# ScrollingTextDisplay.net
KiCad netlist of a schematic drawn in EAGLE
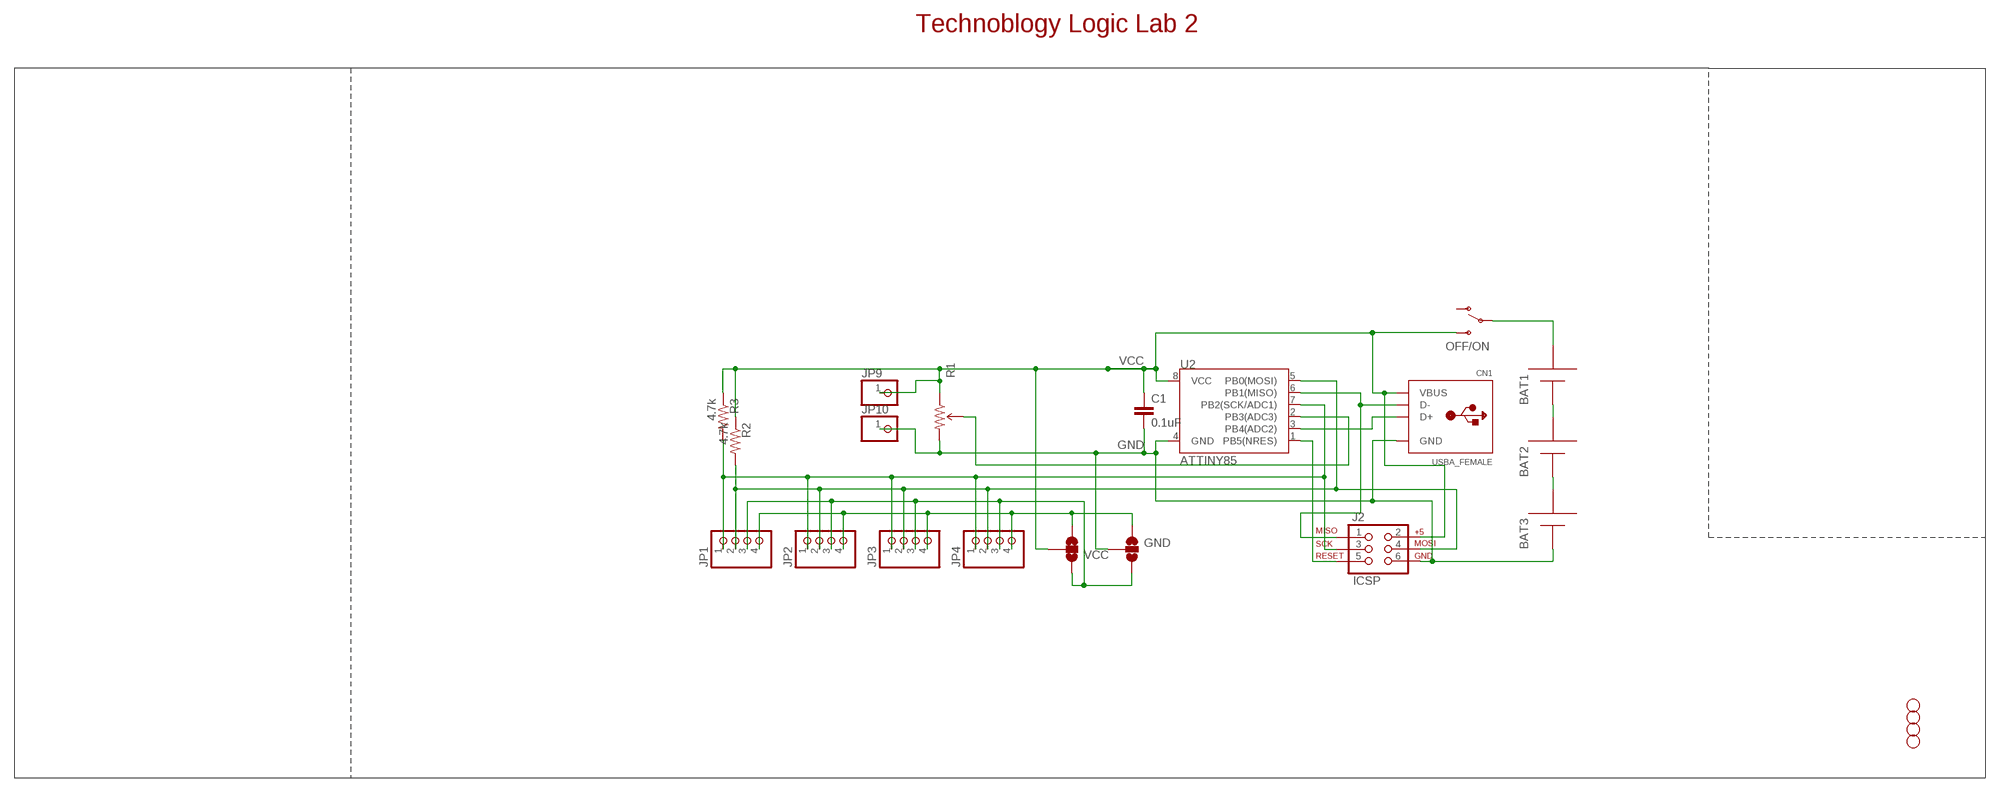
[diagram p0: schematic, sheet 1]

(export (version "E")
  (design (tool "Eeschema 10.0.6"))
  (components
    (comp (ref "BAT1")
      (value "AAA")
      (footprint "eagle-import:12BH412")
      (libsource (lib "eagle-import") (part "AAA"))
    )
    (comp (ref "BAT2")
      (value "AAA")
      (footprint "eagle-import:12BH412")
      (libsource (lib "eagle-import") (part "AAA"))
    )
    (comp (ref "BAT3")
      (value "AAA")
      (footprint "eagle-import:12BH412")
      (libsource (lib "eagle-import") (part "AAA"))
    )
    (comp (ref "C1")
      (value "0.1uF")
      (footprint "eagle-import:CAP-PTH-SMALL-KIT")
      (libsource (lib "eagle-import") (part "0.1UF-50V-20%(PTH)KIT-EZ"))
    )
    (comp (ref "CN1")
      (value "USBA_FEMALE")
      (footprint "eagle-import:USB_HOST-PTH")
      (libsource (lib "eagle-import") (part "USB_TYPEAPTHFML"))
    )
    (comp (ref "GND")
      (value "JUMPER-PAD-3-NOFULL_BOX_SILK")
      (footprint "eagle-import:PAD-JUMPER-3-NO_YES_SILK_FULL_BOX")
      (libsource (lib "eagle-import") (part "JUMPER-PAD-3-NOFULL_BOX_SILK"))
    )
    (comp (ref "J2")
      (value "ICSP")
      (footprint "eagle-import:2X3")
      (libsource (lib "eagle-import") (part "AVR_SPI_PRG_6PTH"))
    )
    (comp (ref "JP1")
      (value "HEADER-1X4ROUND")
      (footprint "eagle-import:1X04_ROUND")
      (libsource (lib "eagle-import") (part "HEADER-1X4ROUND"))
    )
    (comp (ref "JP2")
      (value "HEADER-1X4ROUND")
      (footprint "eagle-import:1X04_ROUND")
      (libsource (lib "eagle-import") (part "HEADER-1X4ROUND"))
    )
    (comp (ref "JP3")
      (value "HEADER-1X4ROUND")
      (footprint "eagle-import:1X04_ROUND")
      (libsource (lib "eagle-import") (part "HEADER-1X4ROUND"))
    )
    (comp (ref "JP4")
      (value "HEADER-1X4ROUND")
      (footprint "eagle-import:1X04_ROUND")
      (libsource (lib "eagle-import") (part "HEADER-1X4ROUND"))
    )
    (comp (ref "JP5")
      (value "STAND-OFF")
      (footprint "eagle-import:STAND-OFF")
      (libsource (lib "eagle-import") (part "STAND-OFF"))
    )
    (comp (ref "JP6")
      (value "STAND-OFF")
      (footprint "eagle-import:STAND-OFF")
      (libsource (lib "eagle-import") (part "STAND-OFF"))
    )
    (comp (ref "JP7")
      (value "STAND-OFF")
      (footprint "eagle-import:STAND-OFF")
      (libsource (lib "eagle-import") (part "STAND-OFF"))
    )
    (comp (ref "JP8")
      (value "STAND-OFF")
      (footprint "eagle-import:STAND-OFF")
      (libsource (lib "eagle-import") (part "STAND-OFF"))
    )
    (comp (ref "JP9")
      (value "HEADER-1X1ROUND")
      (footprint "eagle-import:1X01_ROUND")
      (libsource (lib "eagle-import") (part "HEADER-1X1ROUND"))
    )
    (comp (ref "JP10")
      (value "HEADER-1X1ROUND")
      (footprint "eagle-import:1X01_ROUND")
      (libsource (lib "eagle-import") (part "HEADER-1X1ROUND"))
    )
    (comp (ref "OFF/ON")
      (value "SWITCH-SPDTKIT")
      (footprint "eagle-import:SWITCH-SPDT_KIT")
      (libsource (lib "eagle-import") (part "SWITCH-SPDTKIT"))
    )
    (comp (ref "R1")
      (value "TRIMPOTPTH")
      (footprint "eagle-import:TRIM_POT_PTH")
      (libsource (lib "eagle-import") (part "TRIMPOTPTH"))
    )
    (comp (ref "R2")
      (value "4.7k")
      (footprint "eagle-import:AXIAL-0.3")
      (libsource (lib "eagle-import") (part "RESISTORAXIAL-0.3"))
    )
    (comp (ref "R3")
      (value "4.7k")
      (footprint "eagle-import:AXIAL-0.3")
      (libsource (lib "eagle-import") (part "RESISTORAXIAL-0.3"))
    )
    (comp (ref "U2")
      (value "ATTINY85")
      (footprint "eagle-import:DIP08")
      (libsource (lib "eagle-import") (part "ATTINY45TINY85-20-DIP"))
    )
    (comp (ref "VCC")
      (value "JUMPER-PAD-3-NOFULL_BOX_SILK")
      (footprint "eagle-import:PAD-JUMPER-3-NO_YES_SILK_FULL_BOX")
      (libsource (lib "eagle-import") (part "JUMPER-PAD-3-NOFULL_BOX_SILK"))
    )
  )
  (nets
    (net (code "1") (name "/GND") (class "Default")
      (node (ref "BAT3") (pin "-") (pinfunction "-_-") (pintype "bidirectional"))
      (node (ref "C1") (pin "2") (pinfunction "2_2") (pintype "passive"))
      (node (ref "CN1") (pin "GND") (pinfunction "GND_GND") (pintype "power_in"))
      (node (ref "GND") (pin "2") (pinfunction "2_2") (pintype "passive"))
      (node (ref "J2") (pin "6") (pinfunction "6_6") (pintype "passive"))
      (node (ref "JP10") (pin "1") (pinfunction "1_1") (pintype "passive"))
      (node (ref "R1") (pin "3") (pinfunction "CW_3") (pintype "passive"))
      (node (ref "U2") (pin "4") (pinfunction "GND_4") (pintype "bidirectional"))
    )
    (net (code "2") (name "/VCC") (class "Default")
      (node (ref "C1") (pin "1") (pinfunction "1_1") (pintype "passive"))
      (node (ref "CN1") (pin "VBUS") (pinfunction "VBUS_VBUS") (pintype "power_in"))
      (node (ref "J2") (pin "2") (pinfunction "2_2") (pintype "passive"))
      (node (ref "JP9") (pin "1") (pinfunction "1_1") (pintype "passive"))
      (node (ref "OFF/ON") (pin "3") (pinfunction "S_3") (pintype "passive"))
      (node (ref "R1") (pin "1") (pinfunction "CCW_1") (pintype "passive"))
      (node (ref "R2") (pin "P$1") (pinfunction "1_P$1") (pintype "passive"))
      (node (ref "R3") (pin "P$1") (pinfunction "1_P$1") (pintype "passive"))
      (node (ref "U2") (pin "8") (pinfunction "VCC_8") (pintype "bidirectional"))
      (node (ref "VCC") (pin "2") (pinfunction "2_2") (pintype "passive"))
    )
    (net (code "3") (name "Net-(BAT1-Pad-)") (class "Default")
      (node (ref "BAT1") (pin "-") (pinfunction "-_-") (pintype "bidirectional"))
      (node (ref "BAT2") (pin "+") (pinfunction "+_+") (pintype "bidirectional"))
    )
    (net (code "4") (name "Net-(BAT2-Pad-)") (class "Default")
      (node (ref "BAT2") (pin "-") (pinfunction "-_-") (pintype "bidirectional"))
      (node (ref "BAT3") (pin "+") (pinfunction "+_+") (pintype "bidirectional"))
    )
    (net (code "5") (name "Net-(GND-Pad1)") (class "Default")
      (node (ref "GND") (pin "1") (pinfunction "1_1") (pintype "passive"))
      (node (ref "JP1") (pin "4") (pinfunction "4_4") (pintype "passive"))
      (node (ref "JP2") (pin "4") (pinfunction "4_4") (pintype "passive"))
      (node (ref "JP3") (pin "4") (pinfunction "4_4") (pintype "passive"))
      (node (ref "JP4") (pin "4") (pinfunction "4_4") (pintype "passive"))
      (node (ref "VCC") (pin "3") (pinfunction "3_3") (pintype "passive"))
    )
    (net (code "6") (name "Net-(GND-Pad3)") (class "Default")
      (node (ref "GND") (pin "3") (pinfunction "3_3") (pintype "passive"))
      (node (ref "JP1") (pin "3") (pinfunction "3_3") (pintype "passive"))
      (node (ref "JP2") (pin "3") (pinfunction "3_3") (pintype "passive"))
      (node (ref "JP3") (pin "3") (pinfunction "3_3") (pintype "passive"))
      (node (ref "JP4") (pin "3") (pinfunction "3_3") (pintype "passive"))
      (node (ref "VCC") (pin "1") (pinfunction "1_1") (pintype "passive"))
    )
    (net (code "7") (name "Net-(OFF/ON-P)") (class "Default")
      (node (ref "BAT1") (pin "+") (pinfunction "+_+") (pintype "bidirectional"))
      (node (ref "OFF/ON") (pin "2") (pinfunction "P_2") (pintype "passive"))
    )
    (net (code "8") (name "Net-(R1-WIPER)") (class "Default")
      (node (ref "R1") (pin "2") (pinfunction "WIPER_2") (pintype "passive"))
      (node (ref "U2") (pin "2") (pinfunction "PB3(ADC3)_2") (pintype "bidirectional"))
    )
    (net (code "9") (name "Net-(R2-2)") (class "Default")
      (node (ref "J2") (pin "4") (pinfunction "4_4") (pintype "passive"))
      (node (ref "JP1") (pin "2") (pinfunction "2_2") (pintype "passive"))
      (node (ref "JP2") (pin "2") (pinfunction "2_2") (pintype "passive"))
      (node (ref "JP3") (pin "2") (pinfunction "2_2") (pintype "passive"))
      (node (ref "JP4") (pin "2") (pinfunction "2_2") (pintype "passive"))
      (node (ref "R2") (pin "P$2") (pinfunction "2_P$2") (pintype "passive"))
      (node (ref "U2") (pin "5") (pinfunction "PB0(MOSI)_5") (pintype "bidirectional"))
    )
    (net (code "10") (name "Net-(R3-2)") (class "Default")
      (node (ref "J2") (pin "3") (pinfunction "3_3") (pintype "passive"))
      (node (ref "JP1") (pin "1") (pinfunction "1_1") (pintype "passive"))
      (node (ref "JP2") (pin "1") (pinfunction "1_1") (pintype "passive"))
      (node (ref "JP3") (pin "1") (pinfunction "1_1") (pintype "passive"))
      (node (ref "JP4") (pin "1") (pinfunction "1_1") (pintype "passive"))
      (node (ref "R3") (pin "P$2") (pinfunction "2_P$2") (pintype "passive"))
      (node (ref "U2") (pin "7") (pinfunction "PB2(SCK/ADC1)_7") (pintype "bidirectional"))
    )
    (net (code "11") (name "Net-(U2-PB1(MISO))") (class "Default")
      (node (ref "CN1") (pin "D-") (pinfunction "D-_D-") (pintype "bidirectional"))
      (node (ref "J2") (pin "1") (pinfunction "1_1") (pintype "passive"))
      (node (ref "U2") (pin "6") (pinfunction "PB1(MISO)_6") (pintype "bidirectional"))
    )
    (net (code "12") (name "Net-(U2-PB4(ADC2))") (class "Default")
      (node (ref "CN1") (pin "D+") (pinfunction "D+_D+") (pintype "bidirectional"))
      (node (ref "U2") (pin "3") (pinfunction "PB4(ADC2)_3") (pintype "bidirectional"))
    )
    (net (code "13") (name "Net-(U2-PB5(NRES))") (class "Default")
      (node (ref "J2") (pin "5") (pinfunction "5_5") (pintype "passive"))
      (node (ref "U2") (pin "1") (pinfunction "PB5(NRES)_1") (pintype "bidirectional"))
    )
    (net (code "14") (name "unconnected-(OFF/ON-O-Pad1)") (class "Default")
      (node (ref "OFF/ON") (pin "1") (pinfunction "O_1") (pintype "passive"))
    )
  )
)
